# Rpi_Interface.net
KiCad netlist of a schematic drawn in EAGLE
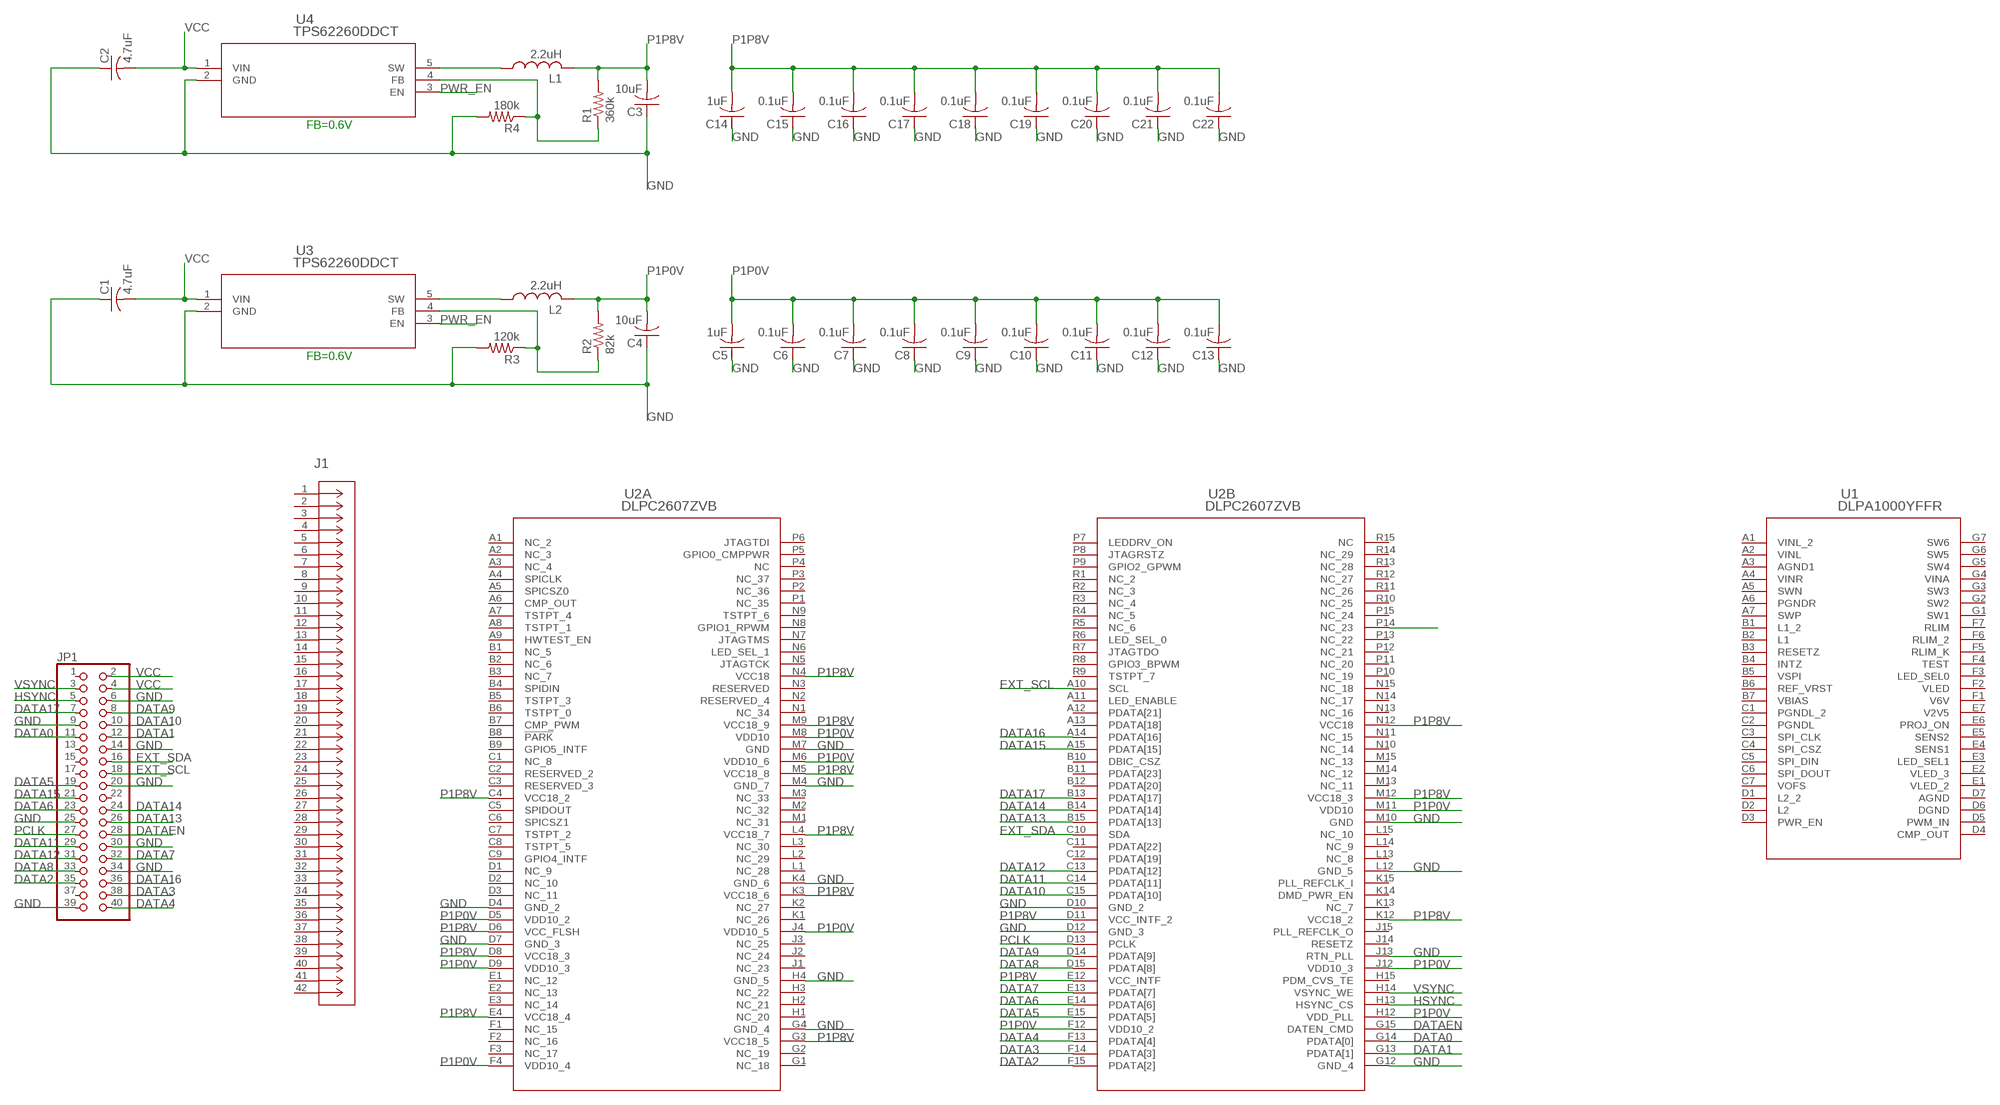
[diagram p0: schematic, sheet 1]

(export (version "E")
  (design (tool "Eeschema 10.0.6"))
  (components
    (comp (ref "C1")
      (value "4.7uF")
      (footprint "eagle-import:C0201")
      (libsource (lib "eagle-import") (part "C-USC0201"))
    )
    (comp (ref "C2")
      (value "4.7uF")
      (footprint "eagle-import:C0201")
      (libsource (lib "eagle-import") (part "C-USC0201"))
    )
    (comp (ref "C3")
      (value "10uF")
      (footprint "eagle-import:C0201")
      (libsource (lib "eagle-import") (part "C-USC0201"))
    )
    (comp (ref "C4")
      (value "10uF")
      (footprint "eagle-import:C0201")
      (libsource (lib "eagle-import") (part "C-USC0201"))
    )
    (comp (ref "C5")
      (value "1uF")
      (footprint "eagle-import:C0201")
      (libsource (lib "eagle-import") (part "C-USC0201"))
    )
    (comp (ref "C6")
      (value "0.1uF")
      (footprint "eagle-import:C0201")
      (libsource (lib "eagle-import") (part "C-USC0201"))
    )
    (comp (ref "C7")
      (value "0.1uF")
      (footprint "eagle-import:C0201")
      (libsource (lib "eagle-import") (part "C-USC0201"))
    )
    (comp (ref "C8")
      (value "0.1uF")
      (footprint "eagle-import:C0201")
      (libsource (lib "eagle-import") (part "C-USC0201"))
    )
    (comp (ref "C9")
      (value "0.1uF")
      (footprint "eagle-import:C0201")
      (libsource (lib "eagle-import") (part "C-USC0201"))
    )
    (comp (ref "C10")
      (value "0.1uF")
      (footprint "eagle-import:C0201")
      (libsource (lib "eagle-import") (part "C-USC0201"))
    )
    (comp (ref "C11")
      (value "0.1uF")
      (footprint "eagle-import:C0201")
      (libsource (lib "eagle-import") (part "C-USC0201"))
    )
    (comp (ref "C12")
      (value "0.1uF")
      (footprint "eagle-import:C0201")
      (libsource (lib "eagle-import") (part "C-USC0201"))
    )
    (comp (ref "C13")
      (value "0.1uF")
      (footprint "eagle-import:C0201")
      (libsource (lib "eagle-import") (part "C-USC0201"))
    )
    (comp (ref "C14")
      (value "1uF")
      (footprint "eagle-import:C0201")
      (libsource (lib "eagle-import") (part "C-USC0201"))
    )
    (comp (ref "C15")
      (value "0.1uF")
      (footprint "eagle-import:C0201")
      (libsource (lib "eagle-import") (part "C-USC0201"))
    )
    (comp (ref "C16")
      (value "0.1uF")
      (footprint "eagle-import:C0201")
      (libsource (lib "eagle-import") (part "C-USC0201"))
    )
    (comp (ref "C17")
      (value "0.1uF")
      (footprint "eagle-import:C0201")
      (libsource (lib "eagle-import") (part "C-USC0201"))
    )
    (comp (ref "C18")
      (value "0.1uF")
      (footprint "eagle-import:C0201")
      (libsource (lib "eagle-import") (part "C-USC0201"))
    )
    (comp (ref "C19")
      (value "0.1uF")
      (footprint "eagle-import:C0201")
      (libsource (lib "eagle-import") (part "C-USC0201"))
    )
    (comp (ref "C20")
      (value "0.1uF")
      (footprint "eagle-import:C0201")
      (libsource (lib "eagle-import") (part "C-USC0201"))
    )
    (comp (ref "C21")
      (value "0.1uF")
      (footprint "eagle-import:C0201")
      (libsource (lib "eagle-import") (part "C-USC0201"))
    )
    (comp (ref "C22")
      (value "0.1uF")
      (footprint "eagle-import:C0201")
      (libsource (lib "eagle-import") (part "C-USC0201"))
    )
    (comp (ref "J1")
      (value "AXT642124DD1")
      (footprint "eagle-import:CONN_AXT642124_PAN")
      (fields (field (name "COPYRIGHT") "Copyright (C) 2018 Accelerated Designs. All rights reserved"))
      (libsource (lib "eagle-import") (part "AXT642124DD1"))
    )
    (comp (ref "JP1")
      (value "PINHD-2X20")
      (footprint "eagle-import:2X20")
      (libsource (lib "eagle-import") (part "PINHD-2X20"))
    )
    (comp (ref "L1")
      (value "2.2uH")
      (footprint "eagle-import:L0201")
      (libsource (lib "eagle-import") (part "L-USL0201"))
    )
    (comp (ref "L2")
      (value "2.2uH")
      (footprint "eagle-import:L0201")
      (libsource (lib "eagle-import") (part "L-USL0201"))
    )
    (comp (ref "R1")
      (value "360k")
      (footprint "eagle-import:0204V")
      (libsource (lib "eagle-import") (part "R-US_0204/2V"))
    )
    (comp (ref "R2")
      (value "82k")
      (footprint "eagle-import:0204V")
      (libsource (lib "eagle-import") (part "R-US_0204/2V"))
    )
    (comp (ref "R3")
      (value "120k")
      (footprint "eagle-import:0204V")
      (libsource (lib "eagle-import") (part "R-US_0204/2V"))
    )
    (comp (ref "R4")
      (value "180k")
      (footprint "eagle-import:0204V")
      (libsource (lib "eagle-import") (part "R-US_0204/2V"))
    )
    (comp (ref "U1")
      (value "DLPA1000YFFR")
      (footprint "eagle-import:YFF49_TEX")
      (fields (field (name "COPYRIGHT") "Copyright (C) 2018 Accelerated Designs. All rights reserved"))
      (libsource (lib "eagle-import") (part "DLPA1000YFFR"))
    )
    (comp (ref "U2")
      (value "DLPC2607ZVB")
      (footprint "eagle-import:ZVB176_TEX")
      (libsource (lib "eagle-import") (part "DLPC2607ZVB"))
    )
    (comp (ref "U3")
      (value "TPS62260DDCT")
      (footprint "eagle-import:DDC5")
      (fields
        (field (name "GENERIC_PART_NUMBER") "TPS62260")
        (field (name "MANUFACTURER") "Texas Instruments")
      )
      (libsource (lib "eagle-import") (part "TPS62260DDCT"))
    )
    (comp (ref "U4")
      (value "TPS62260DDCT")
      (footprint "eagle-import:DDC5")
      (fields
        (field (name "GENERIC_PART_NUMBER") "TPS62260")
        (field (name "MANUFACTURER") "Texas Instruments")
      )
      (libsource (lib "eagle-import") (part "TPS62260DDCT"))
    )
  )
  (nets
    (net (code "1") (name "/AGND") (class "Default")
      (node (ref "U1") (pin "D7") (pinfunction "AGND_D7") (pintype "power_in"))
    )
    (net (code "2") (name "/AGND1") (class "Default")
      (node (ref "U1") (pin "A3") (pinfunction "AGND1_A3") (pintype "power_in"))
    )
    (net (code "3") (name "/DATA0") (class "Default")
      (node (ref "JP1") (pin "11") (pinfunction "11_11") (pintype "passive"))
      (node (ref "U2") (pin "G14") (pinfunction "PDATA[0]_G14") (pintype "input"))
    )
    (net (code "4") (name "/DATA1") (class "Default")
      (node (ref "JP1") (pin "12") (pinfunction "12_12") (pintype "passive"))
      (node (ref "U2") (pin "G13") (pinfunction "PDATA[1]_G13") (pintype "input"))
    )
    (net (code "5") (name "/DATA2") (class "Default")
      (node (ref "JP1") (pin "35") (pinfunction "35_35") (pintype "passive"))
      (node (ref "U2") (pin "F15") (pinfunction "PDATA[2]_F15") (pintype "input"))
    )
    (net (code "6") (name "/DATA3") (class "Default")
      (node (ref "JP1") (pin "38") (pinfunction "38_38") (pintype "passive"))
      (node (ref "U2") (pin "F14") (pinfunction "PDATA[3]_F14") (pintype "input"))
    )
    (net (code "7") (name "/DATA4") (class "Default")
      (node (ref "JP1") (pin "40") (pinfunction "40_40") (pintype "passive"))
      (node (ref "U2") (pin "F13") (pinfunction "PDATA[4]_F13") (pintype "input"))
    )
    (net (code "8") (name "/DATA5") (class "Default")
      (node (ref "JP1") (pin "19") (pinfunction "19_19") (pintype "passive"))
      (node (ref "U2") (pin "E15") (pinfunction "PDATA[5]_E15") (pintype "input"))
    )
    (net (code "9") (name "/DATA6") (class "Default")
      (node (ref "JP1") (pin "23") (pinfunction "23_23") (pintype "passive"))
      (node (ref "U2") (pin "E14") (pinfunction "PDATA[6]_E14") (pintype "input"))
    )
    (net (code "10") (name "/DATA7") (class "Default")
      (node (ref "JP1") (pin "32") (pinfunction "32_32") (pintype "passive"))
      (node (ref "U2") (pin "E13") (pinfunction "PDATA[7]_E13") (pintype "input"))
    )
    (net (code "11") (name "/DATA8") (class "Default")
      (node (ref "JP1") (pin "33") (pinfunction "33_33") (pintype "passive"))
      (node (ref "U2") (pin "D15") (pinfunction "PDATA[8]_D15") (pintype "input"))
    )
    (net (code "12") (name "/DATA9") (class "Default")
      (node (ref "JP1") (pin "8") (pinfunction "8_8") (pintype "passive"))
      (node (ref "U2") (pin "D14") (pinfunction "PDATA[9]_D14") (pintype "input"))
    )
    (net (code "13") (name "/DATA10") (class "Default")
      (node (ref "JP1") (pin "10") (pinfunction "10_10") (pintype "passive"))
      (node (ref "U2") (pin "C15") (pinfunction "PDATA[10]_C15") (pintype "input"))
    )
    (net (code "14") (name "/DATA11") (class "Default")
      (node (ref "JP1") (pin "29") (pinfunction "29_29") (pintype "passive"))
      (node (ref "U2") (pin "C14") (pinfunction "PDATA[11]_C14") (pintype "input"))
    )
    (net (code "15") (name "/DATA12") (class "Default")
      (node (ref "JP1") (pin "31") (pinfunction "31_31") (pintype "passive"))
      (node (ref "U2") (pin "C13") (pinfunction "PDATA[12]_C13") (pintype "input"))
    )
    (net (code "16") (name "/DATA13") (class "Default")
      (node (ref "JP1") (pin "26") (pinfunction "26_26") (pintype "passive"))
      (node (ref "U2") (pin "B15") (pinfunction "PDATA[13]_B15") (pintype "input"))
    )
    (net (code "17") (name "/DATA14") (class "Default")
      (node (ref "JP1") (pin "24") (pinfunction "24_24") (pintype "passive"))
      (node (ref "U2") (pin "B14") (pinfunction "PDATA[14]_B14") (pintype "input"))
    )
    (net (code "18") (name "/DATA15") (class "Default")
      (node (ref "JP1") (pin "21") (pinfunction "21_21") (pintype "passive"))
      (node (ref "U2") (pin "A15") (pinfunction "PDATA[15]_A15") (pintype "input"))
    )
    (net (code "19") (name "/DATA16") (class "Default")
      (node (ref "JP1") (pin "36") (pinfunction "36_36") (pintype "passive"))
      (node (ref "U2") (pin "A14") (pinfunction "PDATA[16]_A14") (pintype "input"))
    )
    (net (code "20") (name "/DATA17") (class "Default")
      (node (ref "JP1") (pin "7") (pinfunction "7_7") (pintype "passive"))
      (node (ref "U2") (pin "B13") (pinfunction "PDATA[17]_B13") (pintype "input"))
    )
    (net (code "21") (name "/DATAEN") (class "Default")
      (node (ref "JP1") (pin "28") (pinfunction "28_28") (pintype "passive"))
      (node (ref "U2") (pin "G15") (pinfunction "DATEN_CMD_G15") (pintype "input"))
    )
    (net (code "22") (name "/DGND") (class "Default")
      (node (ref "U1") (pin "D6") (pinfunction "DGND_D6") (pintype "power_in"))
    )
    (net (code "23") (name "/EXT_SCL") (class "Default")
      (node (ref "JP1") (pin "18") (pinfunction "18_18") (pintype "passive"))
      (node (ref "U2") (pin "A10") (pinfunction "SCL_A10") (pintype "bidirectional"))
    )
    (net (code "24") (name "/EXT_SDA") (class "Default")
      (node (ref "JP1") (pin "16") (pinfunction "16_16") (pintype "passive"))
      (node (ref "U2") (pin "C10") (pinfunction "SDA_C10") (pintype "bidirectional"))
    )
    (net (code "25") (name "/GND") (class "Default")
      (node (ref "C1") (pin "1") (pinfunction "1_1") (pintype "passive"))
      (node (ref "C10") (pin "1") (pinfunction "1_1") (pintype "passive"))
      (node (ref "C11") (pin "1") (pinfunction "1_1") (pintype "passive"))
      (node (ref "C12") (pin "1") (pinfunction "1_1") (pintype "passive"))
      (node (ref "C13") (pin "1") (pinfunction "1_1") (pintype "passive"))
      (node (ref "C14") (pin "1") (pinfunction "1_1") (pintype "passive"))
      (node (ref "C15") (pin "1") (pinfunction "1_1") (pintype "passive"))
      (node (ref "C16") (pin "1") (pinfunction "1_1") (pintype "passive"))
      (node (ref "C17") (pin "1") (pinfunction "1_1") (pintype "passive"))
      (node (ref "C18") (pin "1") (pinfunction "1_1") (pintype "passive"))
      (node (ref "C19") (pin "1") (pinfunction "1_1") (pintype "passive"))
      (node (ref "C2") (pin "1") (pinfunction "1_1") (pintype "passive"))
      (node (ref "C20") (pin "1") (pinfunction "1_1") (pintype "passive"))
      (node (ref "C21") (pin "1") (pinfunction "1_1") (pintype "passive"))
      (node (ref "C22") (pin "1") (pinfunction "1_1") (pintype "passive"))
      (node (ref "C3") (pin "1") (pinfunction "1_1") (pintype "passive"))
      (node (ref "C4") (pin "1") (pinfunction "1_1") (pintype "passive"))
      (node (ref "C5") (pin "1") (pinfunction "1_1") (pintype "passive"))
      (node (ref "C6") (pin "1") (pinfunction "1_1") (pintype "passive"))
      (node (ref "C7") (pin "1") (pinfunction "1_1") (pintype "passive"))
      (node (ref "C8") (pin "1") (pinfunction "1_1") (pintype "passive"))
      (node (ref "C9") (pin "1") (pinfunction "1_1") (pintype "passive"))
      (node (ref "JP1") (pin "14") (pinfunction "14_14") (pintype "passive"))
      (node (ref "JP1") (pin "20") (pinfunction "20_20") (pintype "passive"))
      (node (ref "JP1") (pin "25") (pinfunction "25_25") (pintype "passive"))
      (node (ref "JP1") (pin "30") (pinfunction "30_30") (pintype "passive"))
      (node (ref "JP1") (pin "34") (pinfunction "34_34") (pintype "passive"))
      (node (ref "JP1") (pin "39") (pinfunction "39_39") (pintype "passive"))
      (node (ref "JP1") (pin "6") (pinfunction "6_6") (pintype "passive"))
      (node (ref "JP1") (pin "9") (pinfunction "9_9") (pintype "passive"))
      (node (ref "R3") (pin "2") (pinfunction "2_2") (pintype "passive"))
      (node (ref "R4") (pin "2") (pinfunction "2_2") (pintype "passive"))
      (node (ref "U2") (pin "D10") (pinfunction "GND_2_D10") (pintype "power_in"))
      (node (ref "U2") (pin "D12") (pinfunction "GND_3_D12") (pintype "power_in"))
      (node (ref "U2") (pin "D4") (pinfunction "GND_2_D4") (pintype "power_in"))
      (node (ref "U2") (pin "D7") (pinfunction "GND_3_D7") (pintype "power_in"))
      (node (ref "U2") (pin "G12") (pinfunction "GND_4_G12") (pintype "power_in"))
      (node (ref "U2") (pin "G4") (pinfunction "GND_4_G4") (pintype "power_in"))
      (node (ref "U2") (pin "H4") (pinfunction "GND_5_H4") (pintype "power_in"))
      (node (ref "U2") (pin "J13") (pinfunction "RTN_PLL_J13") (pintype "passive"))
      (node (ref "U2") (pin "K4") (pinfunction "GND_6_K4") (pintype "power_in"))
      (node (ref "U2") (pin "L12") (pinfunction "GND_5_L12") (pintype "power_in"))
      (node (ref "U2") (pin "M10") (pinfunction "GND_M10") (pintype "power_in"))
      (node (ref "U2") (pin "M4") (pinfunction "GND_7_M4") (pintype "power_in"))
      (node (ref "U2") (pin "M7") (pinfunction "GND_M7") (pintype "power_in"))
      (node (ref "U3") (pin "2") (pinfunction "GND_2") (pintype "power_in"))
      (node (ref "U4") (pin "2") (pinfunction "GND_2") (pintype "power_in"))
    )
    (net (code "26") (name "/HSYNC") (class "Default")
      (node (ref "JP1") (pin "5") (pinfunction "5_5") (pintype "passive"))
      (node (ref "U2") (pin "H13") (pinfunction "HSYNC_CS_H13") (pintype "input"))
    )
    (net (code "27") (name "/P1P0V") (class "Default")
      (node (ref "C10") (pin "2") (pinfunction "2_2") (pintype "passive"))
      (node (ref "C11") (pin "2") (pinfunction "2_2") (pintype "passive"))
      (node (ref "C12") (pin "2") (pinfunction "2_2") (pintype "passive"))
      (node (ref "C13") (pin "2") (pinfunction "2_2") (pintype "passive"))
      (node (ref "C4") (pin "2") (pinfunction "2_2") (pintype "passive"))
      (node (ref "C5") (pin "2") (pinfunction "2_2") (pintype "passive"))
      (node (ref "C6") (pin "2") (pinfunction "2_2") (pintype "passive"))
      (node (ref "C7") (pin "2") (pinfunction "2_2") (pintype "passive"))
      (node (ref "C8") (pin "2") (pinfunction "2_2") (pintype "passive"))
      (node (ref "C9") (pin "2") (pinfunction "2_2") (pintype "passive"))
      (node (ref "L2") (pin "2") (pinfunction "2_2") (pintype "passive"))
      (node (ref "R2") (pin "2") (pinfunction "2_2") (pintype "passive"))
      (node (ref "U2") (pin "D5") (pinfunction "VDD10_2_D5") (pintype "power_in"))
      (node (ref "U2") (pin "D9") (pinfunction "VDD10_3_D9") (pintype "power_in"))
      (node (ref "U2") (pin "F12") (pinfunction "VDD10_2_F12") (pintype "power_in"))
      (node (ref "U2") (pin "F4") (pinfunction "VDD10_4_F4") (pintype "power_in"))
      (node (ref "U2") (pin "H12") (pinfunction "VDD_PLL_H12") (pintype "power_in"))
      (node (ref "U2") (pin "J12") (pinfunction "VDD10_3_J12") (pintype "power_in"))
      (node (ref "U2") (pin "J4") (pinfunction "VDD10_5_J4") (pintype "power_in"))
      (node (ref "U2") (pin "M11") (pinfunction "VDD10_M11") (pintype "power_in"))
      (node (ref "U2") (pin "M6") (pinfunction "VDD10_6_M6") (pintype "power_in"))
      (node (ref "U2") (pin "M8") (pinfunction "VDD10_M8") (pintype "power_in"))
    )
    (net (code "28") (name "/P1P8V") (class "Default")
      (node (ref "C14") (pin "2") (pinfunction "2_2") (pintype "passive"))
      (node (ref "C15") (pin "2") (pinfunction "2_2") (pintype "passive"))
      (node (ref "C16") (pin "2") (pinfunction "2_2") (pintype "passive"))
      (node (ref "C17") (pin "2") (pinfunction "2_2") (pintype "passive"))
      (node (ref "C18") (pin "2") (pinfunction "2_2") (pintype "passive"))
      (node (ref "C19") (pin "2") (pinfunction "2_2") (pintype "passive"))
      (node (ref "C20") (pin "2") (pinfunction "2_2") (pintype "passive"))
      (node (ref "C21") (pin "2") (pinfunction "2_2") (pintype "passive"))
      (node (ref "C22") (pin "2") (pinfunction "2_2") (pintype "passive"))
      (node (ref "C3") (pin "2") (pinfunction "2_2") (pintype "passive"))
      (node (ref "L1") (pin "2") (pinfunction "2_2") (pintype "passive"))
      (node (ref "R1") (pin "2") (pinfunction "2_2") (pintype "passive"))
      (node (ref "U2") (pin "C4") (pinfunction "VCC18_2_C4") (pintype "power_in"))
      (node (ref "U2") (pin "D11") (pinfunction "VCC_INTF_2_D11") (pintype "power_in"))
      (node (ref "U2") (pin "D6") (pinfunction "VCC_FLSH_D6") (pintype "power_in"))
      (node (ref "U2") (pin "D8") (pinfunction "VCC18_3_D8") (pintype "power_in"))
      (node (ref "U2") (pin "E12") (pinfunction "VCC_INTF_E12") (pintype "power_in"))
      (node (ref "U2") (pin "E4") (pinfunction "VCC18_4_E4") (pintype "power_in"))
      (node (ref "U2") (pin "G3") (pinfunction "VCC18_5_G3") (pintype "power_in"))
      (node (ref "U2") (pin "K12") (pinfunction "VCC18_2_K12") (pintype "power_in"))
      (node (ref "U2") (pin "K3") (pinfunction "VCC18_6_K3") (pintype "power_in"))
      (node (ref "U2") (pin "L4") (pinfunction "VCC18_7_L4") (pintype "power_in"))
      (node (ref "U2") (pin "M12") (pinfunction "VCC18_3_M12") (pintype "power_in"))
      (node (ref "U2") (pin "M5") (pinfunction "VCC18_8_M5") (pintype "power_in"))
      (node (ref "U2") (pin "M9") (pinfunction "VCC18_9_M9") (pintype "power_in"))
      (node (ref "U2") (pin "N12") (pinfunction "VCC18_N12") (pintype "power_in"))
      (node (ref "U2") (pin "N4") (pinfunction "VCC18_N4") (pintype "power_in"))
    )
    (net (code "29") (name "/PCLK") (class "Default")
      (node (ref "JP1") (pin "27") (pinfunction "27_27") (pintype "passive"))
      (node (ref "U2") (pin "D13") (pinfunction "PCLK_D13") (pintype "input"))
    )
    (net (code "30") (name "/PGNDL") (class "Default")
      (node (ref "U1") (pin "C2") (pinfunction "PGNDL_C2") (pintype "power_in"))
    )
    (net (code "31") (name "/PGNDL_2") (class "Default")
      (node (ref "U1") (pin "C1") (pinfunction "PGNDL_2_C1") (pintype "power_in"))
    )
    (net (code "32") (name "/PGNDR") (class "Default")
      (node (ref "U1") (pin "A6") (pinfunction "PGNDR_A6") (pintype "power_in"))
    )
    (net (code "33") (name "/PWR_EN") (class "Default")
      (node (ref "U3") (pin "3") (pinfunction "EN_3") (pintype "input"))
      (node (ref "U4") (pin "3") (pinfunction "EN_3") (pintype "input"))
    )
    (net (code "34") (name "/VCC") (class "Default")
      (node (ref "C1") (pin "2") (pinfunction "2_2") (pintype "passive"))
      (node (ref "C2") (pin "2") (pinfunction "2_2") (pintype "passive"))
      (node (ref "JP1") (pin "2") (pinfunction "2_2") (pintype "passive"))
      (node (ref "JP1") (pin "4") (pinfunction "4_4") (pintype "passive"))
      (node (ref "U3") (pin "1") (pinfunction "VIN_1") (pintype "power_in"))
      (node (ref "U4") (pin "1") (pinfunction "VIN_1") (pintype "power_in"))
    )
    (net (code "35") (name "/VSPI") (class "Default")
      (node (ref "U1") (pin "B5") (pinfunction "VSPI_B5") (pintype "power_in"))
    )
    (net (code "36") (name "/VSYNC") (class "Default")
      (node (ref "JP1") (pin "3") (pinfunction "3_3") (pintype "passive"))
      (node (ref "U2") (pin "H14") (pinfunction "VSYNC_WE_H14") (pintype "input"))
    )
    (net (code "37") (name "Net-(U3-FB)") (class "Default")
      (node (ref "R2") (pin "1") (pinfunction "1_1") (pintype "passive"))
      (node (ref "R3") (pin "1") (pinfunction "1_1") (pintype "passive"))
      (node (ref "U3") (pin "4") (pinfunction "FB_4") (pintype "input"))
    )
    (net (code "38") (name "Net-(U3-SW)") (class "Default")
      (node (ref "L2") (pin "1") (pinfunction "1_1") (pintype "passive"))
      (node (ref "U3") (pin "5") (pinfunction "SW_5") (pintype "output"))
    )
    (net (code "39") (name "Net-(U4-FB)") (class "Default")
      (node (ref "R1") (pin "1") (pinfunction "1_1") (pintype "passive"))
      (node (ref "R4") (pin "1") (pinfunction "1_1") (pintype "passive"))
      (node (ref "U4") (pin "4") (pinfunction "FB_4") (pintype "input"))
    )
    (net (code "40") (name "Net-(U4-SW)") (class "Default")
      (node (ref "L1") (pin "1") (pinfunction "1_1") (pintype "passive"))
      (node (ref "U4") (pin "5") (pinfunction "SW_5") (pintype "output"))
    )
    (net (code "41") (name "unconnected-(J1-Pad1)") (class "Default")
      (node (ref "J1") (pin "1") (pinfunction "1_1") (pintype "passive"))
    )
    (net (code "42") (name "unconnected-(J1-Pad2)") (class "Default")
      (node (ref "J1") (pin "2") (pinfunction "2_2") (pintype "passive"))
    )
    (net (code "43") (name "unconnected-(J1-Pad3)") (class "Default")
      (node (ref "J1") (pin "3") (pinfunction "3_3") (pintype "passive"))
    )
    (net (code "44") (name "unconnected-(J1-Pad4)") (class "Default")
      (node (ref "J1") (pin "4") (pinfunction "4_4") (pintype "passive"))
    )
    (net (code "45") (name "unconnected-(J1-Pad5)") (class "Default")
      (node (ref "J1") (pin "5") (pinfunction "5_5") (pintype "passive"))
    )
    (net (code "46") (name "unconnected-(J1-Pad6)") (class "Default")
      (node (ref "J1") (pin "6") (pinfunction "6_6") (pintype "passive"))
    )
    (net (code "47") (name "unconnected-(J1-Pad7)") (class "Default")
      (node (ref "J1") (pin "7") (pinfunction "7_7") (pintype "passive"))
    )
    (net (code "48") (name "unconnected-(J1-Pad8)") (class "Default")
      (node (ref "J1") (pin "8") (pinfunction "8_8") (pintype "passive"))
    )
    (net (code "49") (name "unconnected-(J1-Pad9)") (class "Default")
      (node (ref "J1") (pin "9") (pinfunction "9_9") (pintype "passive"))
    )
    (net (code "50") (name "unconnected-(J1-Pad10)") (class "Default")
      (node (ref "J1") (pin "10") (pinfunction "10_10") (pintype "passive"))
    )
    (net (code "51") (name "unconnected-(J1-Pad11)") (class "Default")
      (node (ref "J1") (pin "11") (pinfunction "11_11") (pintype "passive"))
    )
    (net (code "52") (name "unconnected-(J1-Pad12)") (class "Default")
      (node (ref "J1") (pin "12") (pinfunction "12_12") (pintype "passive"))
    )
    (net (code "53") (name "unconnected-(J1-Pad13)") (class "Default")
      (node (ref "J1") (pin "13") (pinfunction "13_13") (pintype "passive"))
    )
    (net (code "54") (name "unconnected-(J1-Pad14)") (class "Default")
      (node (ref "J1") (pin "14") (pinfunction "14_14") (pintype "passive"))
    )
    (net (code "55") (name "unconnected-(J1-Pad15)") (class "Default")
      (node (ref "J1") (pin "15") (pinfunction "15_15") (pintype "passive"))
    )
    (net (code "56") (name "unconnected-(J1-Pad16)") (class "Default")
      (node (ref "J1") (pin "16") (pinfunction "16_16") (pintype "passive"))
    )
    (net (code "57") (name "unconnected-(J1-Pad17)") (class "Default")
      (node (ref "J1") (pin "17") (pinfunction "17_17") (pintype "passive"))
    )
    (net (code "58") (name "unconnected-(J1-Pad18)") (class "Default")
      (node (ref "J1") (pin "18") (pinfunction "18_18") (pintype "passive"))
    )
    (net (code "59") (name "unconnected-(J1-Pad19)") (class "Default")
      (node (ref "J1") (pin "19") (pinfunction "19_19") (pintype "passive"))
    )
    (net (code "60") (name "unconnected-(J1-Pad20)") (class "Default")
      (node (ref "J1") (pin "20") (pinfunction "20_20") (pintype "passive"))
    )
    (net (code "61") (name "unconnected-(J1-Pad21)") (class "Default")
      (node (ref "J1") (pin "21") (pinfunction "21_21") (pintype "passive"))
    )
    (net (code "62") (name "unconnected-(J1-Pad22)") (class "Default")
      (node (ref "J1") (pin "22") (pinfunction "22_22") (pintype "passive"))
    )
    (net (code "63") (name "unconnected-(J1-Pad23)") (class "Default")
      (node (ref "J1") (pin "23") (pinfunction "23_23") (pintype "passive"))
    )
    (net (code "64") (name "unconnected-(J1-Pad24)") (class "Default")
      (node (ref "J1") (pin "24") (pinfunction "24_24") (pintype "passive"))
    )
    (net (code "65") (name "unconnected-(J1-Pad25)") (class "Default")
      (node (ref "J1") (pin "25") (pinfunction "25_25") (pintype "passive"))
    )
    (net (code "66") (name "unconnected-(J1-Pad26)") (class "Default")
      (node (ref "J1") (pin "26") (pinfunction "26_26") (pintype "passive"))
    )
    (net (code "67") (name "unconnected-(J1-Pad27)") (class "Default")
      (node (ref "J1") (pin "27") (pinfunction "27_27") (pintype "passive"))
    )
    (net (code "68") (name "unconnected-(J1-Pad28)") (class "Default")
      (node (ref "J1") (pin "28") (pinfunction "28_28") (pintype "passive"))
    )
    (net (code "69") (name "unconnected-(J1-Pad29)") (class "Default")
      (node (ref "J1") (pin "29") (pinfunction "29_29") (pintype "passive"))
    )
    (net (code "70") (name "unconnected-(J1-Pad30)") (class "Default")
      (node (ref "J1") (pin "30") (pinfunction "30_30") (pintype "passive"))
    )
    (net (code "71") (name "unconnected-(J1-Pad31)") (class "Default")
      (node (ref "J1") (pin "31") (pinfunction "31_31") (pintype "passive"))
    )
    (net (code "72") (name "unconnected-(J1-Pad32)") (class "Default")
      (node (ref "J1") (pin "32") (pinfunction "32_32") (pintype "passive"))
    )
    (net (code "73") (name "unconnected-(J1-Pad33)") (class "Default")
      (node (ref "J1") (pin "33") (pinfunction "33_33") (pintype "passive"))
    )
    (net (code "74") (name "unconnected-(J1-Pad34)") (class "Default")
      (node (ref "J1") (pin "34") (pinfunction "34_34") (pintype "passive"))
    )
    (net (code "75") (name "unconnected-(J1-Pad35)") (class "Default")
      (node (ref "J1") (pin "35") (pinfunction "35_35") (pintype "passive"))
    )
    (net (code "76") (name "unconnected-(J1-Pad36)") (class "Default")
      (node (ref "J1") (pin "36") (pinfunction "36_36") (pintype "passive"))
    )
    (net (code "77") (name "unconnected-(J1-Pad37)") (class "Default")
      (node (ref "J1") (pin "37") (pinfunction "37_37") (pintype "passive"))
    )
    (net (code "78") (name "unconnected-(J1-Pad38)") (class "Default")
      (node (ref "J1") (pin "38") (pinfunction "38_38") (pintype "passive"))
    )
    (net (code "79") (name "unconnected-(J1-Pad39)") (class "Default")
      (node (ref "J1") (pin "39") (pinfunction "39_39") (pintype "passive"))
    )
    (net (code "80") (name "unconnected-(J1-Pad40)") (class "Default")
      (node (ref "J1") (pin "40") (pinfunction "40_40") (pintype "passive"))
    )
    (net (code "81") (name "unconnected-(J1-Pad41)") (class "Default")
      (node (ref "J1") (pin "41") (pinfunction "41_41") (pintype "passive"))
    )
    (net (code "82") (name "unconnected-(J1-Pad42)") (class "Default")
      (node (ref "J1") (pin "42") (pinfunction "42_42") (pintype "passive"))
    )
    (net (code "83") (name "unconnected-(JP1-Pad1)") (class "Default")
      (node (ref "JP1") (pin "1") (pinfunction "1_1") (pintype "passive"))
    )
    (net (code "84") (name "unconnected-(JP1-Pad13)") (class "Default")
      (node (ref "JP1") (pin "13") (pinfunction "13_13") (pintype "passive"))
    )
    (net (code "85") (name "unconnected-(JP1-Pad15)") (class "Default")
      (node (ref "JP1") (pin "15") (pinfunction "15_15") (pintype "passive"))
    )
    (net (code "86") (name "unconnected-(JP1-Pad17)") (class "Default")
      (node (ref "JP1") (pin "17") (pinfunction "17_17") (pintype "passive"))
    )
    (net (code "87") (name "unconnected-(JP1-Pad22)") (class "Default")
      (node (ref "JP1") (pin "22") (pinfunction "22_22") (pintype "passive"))
    )
    (net (code "88") (name "unconnected-(JP1-Pad37)") (class "Default")
      (node (ref "JP1") (pin "37") (pinfunction "37_37") (pintype "passive"))
    )
    (net (code "89") (name "unconnected-(U1-CMP_OUT-PadD4)") (class "Default")
      (node (ref "U1") (pin "D4") (pinfunction "CMP_OUT_D4") (pintype "output"))
    )
    (net (code "90") (name "unconnected-(U1-INTZ-PadB4)") (class "Default")
      (node (ref "U1") (pin "B4") (pinfunction "INTZ_B4") (pintype "output"))
    )
    (net (code "91") (name "unconnected-(U1-L1-PadB2)") (class "Default")
      (node (ref "U1") (pin "B2") (pinfunction "L1_B2") (pintype "input"))
    )
    (net (code "92") (name "unconnected-(U1-L1_2-PadB1)") (class "Default")
      (node (ref "U1") (pin "B1") (pinfunction "L1_2_B1") (pintype "input"))
    )
    (net (code "93") (name "unconnected-(U1-L2-PadD2)") (class "Default")
      (node (ref "U1") (pin "D2") (pinfunction "L2_D2") (pintype "input"))
    )
    (net (code "94") (name "unconnected-(U1-L2_2-PadD1)") (class "Default")
      (node (ref "U1") (pin "D1") (pinfunction "L2_2_D1") (pintype "input"))
    )
    (net (code "95") (name "unconnected-(U1-LED_SEL0-PadF3)") (class "Default")
      (node (ref "U1") (pin "F3") (pinfunction "LED_SEL0_F3") (pintype "input"))
    )
    (net (code "96") (name "unconnected-(U1-LED_SEL1-PadE3)") (class "Default")
      (node (ref "U1") (pin "E3") (pinfunction "LED_SEL1_E3") (pintype "input"))
    )
    (net (code "97") (name "unconnected-(U1-PROJ_ON-PadE6)") (class "Default")
      (node (ref "U1") (pin "E6") (pinfunction "PROJ_ON_E6") (pintype "input"))
    )
    (net (code "98") (name "unconnected-(U1-PWM_IN-PadD5)") (class "Default")
      (node (ref "U1") (pin "D5") (pinfunction "PWM_IN_D5") (pintype "input"))
    )
    (net (code "99") (name "unconnected-(U1-PWR_EN-PadD3)") (class "Default")
      (node (ref "U1") (pin "D3") (pinfunction "PWR_EN_D3") (pintype "output"))
    )
    (net (code "100") (name "unconnected-(U1-REF_VRST-PadB6)") (class "Default")
      (node (ref "U1") (pin "B6") (pinfunction "REF_VRST_B6") (pintype "input"))
    )
    (net (code "101") (name "unconnected-(U1-RESETZ-PadB3)") (class "Default")
      (node (ref "U1") (pin "B3") (pinfunction "RESETZ_B3") (pintype "output"))
    )
    (net (code "102") (name "unconnected-(U1-RLIM-PadF7)") (class "Default")
      (node (ref "U1") (pin "F7") (pinfunction "RLIM_F7") (pintype "output"))
    )
    (net (code "103") (name "unconnected-(U1-RLIM_2-PadF6)") (class "Default")
      (node (ref "U1") (pin "F6") (pinfunction "RLIM_2_F6") (pintype "output"))
    )
    (net (code "104") (name "unconnected-(U1-RLIM_K-PadF5)") (class "Default")
      (node (ref "U1") (pin "F5") (pinfunction "RLIM_K_F5") (pintype "input"))
    )
    (net (code "105") (name "unconnected-(U1-SENS1-PadE4)") (class "Default")
      (node (ref "U1") (pin "E4") (pinfunction "SENS1_E4") (pintype "input"))
    )
    (net (code "106") (name "unconnected-(U1-SENS2-PadE5)") (class "Default")
      (node (ref "U1") (pin "E5") (pinfunction "SENS2_E5") (pintype "input"))
    )
    (net (code "107") (name "unconnected-(U1-SPI_CLK-PadC3)") (class "Default")
      (node (ref "U1") (pin "C3") (pinfunction "SPI_CLK_C3") (pintype "input"))
    )
    (net (code "108") (name "unconnected-(U1-SPI_CSZ-PadC4)") (class "Default")
      (node (ref "U1") (pin "C4") (pinfunction "SPI_CSZ_C4") (pintype "input"))
    )
    (net (code "109") (name "unconnected-(U1-SPI_DIN-PadC5)") (class "Default")
      (node (ref "U1") (pin "C5") (pinfunction "SPI_DIN_C5") (pintype "input"))
    )
    (net (code "110") (name "unconnected-(U1-SPI_DOUT-PadC6)") (class "Default")
      (node (ref "U1") (pin "C6") (pinfunction "SPI_DOUT_C6") (pintype "output"))
    )
    (net (code "111") (name "unconnected-(U1-SW1-PadG1)") (class "Default")
      (node (ref "U1") (pin "G1") (pinfunction "SW1_G1") (pintype "output"))
    )
    (net (code "112") (name "unconnected-(U1-SW2-PadG2)") (class "Default")
      (node (ref "U1") (pin "G2") (pinfunction "SW2_G2") (pintype "output"))
    )
    (net (code "113") (name "unconnected-(U1-SW3-PadG3)") (class "Default")
      (node (ref "U1") (pin "G3") (pinfunction "SW3_G3") (pintype "output"))
    )
    (net (code "114") (name "unconnected-(U1-SW4-PadG5)") (class "Default")
      (node (ref "U1") (pin "G5") (pinfunction "SW4_G5") (pintype "output"))
    )
    (net (code "115") (name "unconnected-(U1-SW5-PadG6)") (class "Default")
      (node (ref "U1") (pin "G6") (pinfunction "SW5_G6") (pintype "output"))
    )
    (net (code "116") (name "unconnected-(U1-SW6-PadG7)") (class "Default")
      (node (ref "U1") (pin "G7") (pinfunction "SW6_G7") (pintype "output"))
    )
    (net (code "117") (name "unconnected-(U1-SWN-PadA5)") (class "Default")
      (node (ref "U1") (pin "A5") (pinfunction "SWN_A5") (pintype "input"))
    )
    (net (code "118") (name "unconnected-(U1-SWP-PadA7)") (class "Default")
      (node (ref "U1") (pin "A7") (pinfunction "SWP_A7") (pintype "input"))
    )
    (net (code "119") (name "unconnected-(U1-TEST-PadF4)") (class "Default")
      (node (ref "U1") (pin "F4") (pinfunction "TEST_F4") (pintype "input"))
    )
    (net (code "120") (name "unconnected-(U1-V2V5-PadE7)") (class "Default")
      (node (ref "U1") (pin "E7") (pinfunction "V2V5_E7") (pintype "output"))
    )
    (net (code "121") (name "unconnected-(U1-V6V-PadF1)") (class "Default")
      (node (ref "U1") (pin "F1") (pinfunction "V6V_F1") (pintype "output"))
    )
    (net (code "122") (name "unconnected-(U1-VBIAS-PadB7)") (class "Default")
      (node (ref "U1") (pin "B7") (pinfunction "VBIAS_B7") (pintype "output"))
    )
    (net (code "123") (name "unconnected-(U1-VINA-PadG4)") (class "Default")
      (node (ref "U1") (pin "G4") (pinfunction "VINA_G4") (pintype "input"))
    )
    (net (code "124") (name "unconnected-(U1-VINL-PadA2)") (class "Default")
      (node (ref "U1") (pin "A2") (pinfunction "VINL_A2") (pintype "input"))
    )
    (net (code "125") (name "unconnected-(U1-VINL_2-PadA1)") (class "Default")
      (node (ref "U1") (pin "A1") (pinfunction "VINL_2_A1") (pintype "input"))
    )
    (net (code "126") (name "unconnected-(U1-VINR-PadA4)") (class "Default")
      (node (ref "U1") (pin "A4") (pinfunction "VINR_A4") (pintype "input"))
    )
    (net (code "127") (name "unconnected-(U1-VLED-PadF2)") (class "Default")
      (node (ref "U1") (pin "F2") (pinfunction "VLED_F2") (pintype "output"))
    )
    (net (code "128") (name "unconnected-(U1-VLED_2-PadE1)") (class "Default")
      (node (ref "U1") (pin "E1") (pinfunction "VLED_2_E1") (pintype "output"))
    )
    (net (code "129") (name "unconnected-(U1-VLED_3-PadE2)") (class "Default")
      (node (ref "U1") (pin "E2") (pinfunction "VLED_3_E2") (pintype "output"))
    )
    (net (code "130") (name "unconnected-(U1-VOFS-PadC7)") (class "Default")
      (node (ref "U1") (pin "C7") (pinfunction "VOFS_C7") (pintype "output"))
    )
    (net (code "131") (name "unconnected-(U2A-CMP_OUT-PadA6)") (class "Default")
      (node (ref "U2") (pin "A6") (pinfunction "CMP_OUT_A6") (pintype "input"))
    )
    (net (code "132") (name "unconnected-(U2A-CMP_PWM-PadB7)") (class "Default")
      (node (ref "U2") (pin "B7") (pinfunction "CMP_PWM_B7") (pintype "output"))
    )
    (net (code "133") (name "unconnected-(U2A-GPIO0_CMPPWR-PadP5)") (class "Default")
      (node (ref "U2") (pin "P5") (pinfunction "GPIO0_CMPPWR_P5") (pintype "bidirectional"))
    )
    (net (code "134") (name "unconnected-(U2A-GPIO1_RPWM-PadN8)") (class "Default")
      (node (ref "U2") (pin "N8") (pinfunction "GPIO1_RPWM_N8") (pintype "output"))
    )
    (net (code "135") (name "unconnected-(U2A-GPIO4_INTF-PadC9)") (class "Default")
      (node (ref "U2") (pin "C9") (pinfunction "GPIO4_INTF_C9") (pintype "bidirectional"))
    )
    (net (code "136") (name "unconnected-(U2A-GPIO5_INTF-PadB9)") (class "Default")
      (node (ref "U2") (pin "B9") (pinfunction "GPIO5_INTF_B9") (pintype "bidirectional"))
    )
    (net (code "137") (name "unconnected-(U2A-HWTEST_EN-PadA9)") (class "Default")
      (node (ref "U2") (pin "A9") (pinfunction "HWTEST_EN_A9") (pintype "input"))
    )
    (net (code "138") (name "unconnected-(U2A-JTAGTCK-PadN5)") (class "Default")
      (node (ref "U2") (pin "N5") (pinfunction "JTAGTCK_N5") (pintype "input"))
    )
    (net (code "139") (name "unconnected-(U2A-JTAGTDI-PadP6)") (class "Default")
      (node (ref "U2") (pin "P6") (pinfunction "JTAGTDI_P6") (pintype "input"))
    )
    (net (code "140") (name "unconnected-(U2A-JTAGTMS-PadN7)") (class "Default")
      (node (ref "U2") (pin "N7") (pinfunction "JTAGTMS_N7") (pintype "input"))
    )
    (net (code "141") (name "unconnected-(U2A-LED_SEL_1-PadN6)") (class "Default")
      (node (ref "U2") (pin "N6") (pinfunction "LED_SEL_1_N6") (pintype "output"))
    )
    (net (code "142") (name "unconnected-(U2A-NC-PadP4)") (class "Default")
      (node (ref "U2") (pin "P4") (pinfunction "NC_P4") (pintype "no_connect"))
    )
    (net (code "143") (name "unconnected-(U2A-NC_2-PadA1)") (class "Default")
      (node (ref "U2") (pin "A1") (pinfunction "NC_2_A1") (pintype "no_connect"))
    )
    (net (code "144") (name "unconnected-(U2A-NC_3-PadA2)") (class "Default")
      (node (ref "U2") (pin "A2") (pinfunction "NC_3_A2") (pintype "no_connect"))
    )
    (net (code "145") (name "unconnected-(U2A-NC_4-PadA3)") (class "Default")
      (node (ref "U2") (pin "A3") (pinfunction "NC_4_A3") (pintype "no_connect"))
    )
    (net (code "146") (name "unconnected-(U2A-NC_5-PadB1)") (class "Default")
      (node (ref "U2") (pin "B1") (pinfunction "NC_5_B1") (pintype "no_connect"))
    )
    (net (code "147") (name "unconnected-(U2A-NC_6-PadB2)") (class "Default")
      (node (ref "U2") (pin "B2") (pinfunction "NC_6_B2") (pintype "no_connect"))
    )
    (net (code "148") (name "unconnected-(U2A-NC_7-PadB3)") (class "Default")
      (node (ref "U2") (pin "B3") (pinfunction "NC_7_B3") (pintype "no_connect"))
    )
    (net (code "149") (name "unconnected-(U2A-NC_8-PadC1)") (class "Default")
      (node (ref "U2") (pin "C1") (pinfunction "NC_8_C1") (pintype "no_connect"))
    )
    (net (code "150") (name "unconnected-(U2A-NC_9-PadD1)") (class "Default")
      (node (ref "U2") (pin "D1") (pinfunction "NC_9_D1") (pintype "no_connect"))
    )
    (net (code "151") (name "unconnected-(U2A-NC_10-PadD2)") (class "Default")
      (node (ref "U2") (pin "D2") (pinfunction "NC_10_D2") (pintype "no_connect"))
    )
    (net (code "152") (name "unconnected-(U2A-NC_11-PadD3)") (class "Default")
      (node (ref "U2") (pin "D3") (pinfunction "NC_11_D3") (pintype "no_connect"))
    )
    (net (code "153") (name "unconnected-(U2A-NC_12-PadE1)") (class "Default")
      (node (ref "U2") (pin "E1") (pinfunction "NC_12_E1") (pintype "no_connect"))
    )
    (net (code "154") (name "unconnected-(U2A-NC_13-PadE2)") (class "Default")
      (node (ref "U2") (pin "E2") (pinfunction "NC_13_E2") (pintype "no_connect"))
    )
    (net (code "155") (name "unconnected-(U2A-NC_14-PadE3)") (class "Default")
      (node (ref "U2") (pin "E3") (pinfunction "NC_14_E3") (pintype "no_connect"))
    )
    (net (code "156") (name "unconnected-(U2A-NC_15-PadF1)") (class "Default")
      (node (ref "U2") (pin "F1") (pinfunction "NC_15_F1") (pintype "no_connect"))
    )
    (net (code "157") (name "unconnected-(U2A-NC_16-PadF2)") (class "Default")
      (node (ref "U2") (pin "F2") (pinfunction "NC_16_F2") (pintype "no_connect"))
    )
    (net (code "158") (name "unconnected-(U2A-NC_17-PadF3)") (class "Default")
      (node (ref "U2") (pin "F3") (pinfunction "NC_17_F3") (pintype "no_connect"))
    )
    (net (code "159") (name "unconnected-(U2A-NC_18-PadG1)") (class "Default")
      (node (ref "U2") (pin "G1") (pinfunction "NC_18_G1") (pintype "no_connect"))
    )
    (net (code "160") (name "unconnected-(U2A-NC_19-PadG2)") (class "Default")
      (node (ref "U2") (pin "G2") (pinfunction "NC_19_G2") (pintype "no_connect"))
    )
    (net (code "161") (name "unconnected-(U2A-NC_20-PadH1)") (class "Default")
      (node (ref "U2") (pin "H1") (pinfunction "NC_20_H1") (pintype "no_connect"))
    )
    (net (code "162") (name "unconnected-(U2A-NC_21-PadH2)") (class "Default")
      (node (ref "U2") (pin "H2") (pinfunction "NC_21_H2") (pintype "no_connect"))
    )
    (net (code "163") (name "unconnected-(U2A-NC_22-PadH3)") (class "Default")
      (node (ref "U2") (pin "H3") (pinfunction "NC_22_H3") (pintype "no_connect"))
    )
    (net (code "164") (name "unconnected-(U2A-NC_23-PadJ1)") (class "Default")
      (node (ref "U2") (pin "J1") (pinfunction "NC_23_J1") (pintype "no_connect"))
    )
    (net (code "165") (name "unconnected-(U2A-NC_24-PadJ2)") (class "Default")
      (node (ref "U2") (pin "J2") (pinfunction "NC_24_J2") (pintype "no_connect"))
    )
    (net (code "166") (name "unconnected-(U2A-NC_25-PadJ3)") (class "Default")
      (node (ref "U2") (pin "J3") (pinfunction "NC_25_J3") (pintype "no_connect"))
    )
    (net (code "167") (name "unconnected-(U2A-NC_26-PadK1)") (class "Default")
      (node (ref "U2") (pin "K1") (pinfunction "NC_26_K1") (pintype "no_connect"))
    )
    (net (code "168") (name "unconnected-(U2A-NC_27-PadK2)") (class "Default")
      (node (ref "U2") (pin "K2") (pinfunction "NC_27_K2") (pintype "no_connect"))
    )
    (net (code "169") (name "unconnected-(U2A-NC_28-PadL1)") (class "Default")
      (node (ref "U2") (pin "L1") (pinfunction "NC_28_L1") (pintype "no_connect"))
    )
    (net (code "170") (name "unconnected-(U2A-NC_29-PadL2)") (class "Default")
      (node (ref "U2") (pin "L2") (pinfunction "NC_29_L2") (pintype "no_connect"))
    )
    (net (code "171") (name "unconnected-(U2A-NC_30-PadL3)") (class "Default")
      (node (ref "U2") (pin "L3") (pinfunction "NC_30_L3") (pintype "no_connect"))
    )
    (net (code "172") (name "unconnected-(U2A-NC_31-PadM1)") (class "Default")
      (node (ref "U2") (pin "M1") (pinfunction "NC_31_M1") (pintype "no_connect"))
    )
    (net (code "173") (name "unconnected-(U2A-NC_32-PadM2)") (class "Default")
      (node (ref "U2") (pin "M2") (pinfunction "NC_32_M2") (pintype "no_connect"))
    )
    (net (code "174") (name "unconnected-(U2A-NC_33-PadM3)") (class "Default")
      (node (ref "U2") (pin "M3") (pinfunction "NC_33_M3") (pintype "no_connect"))
    )
    (net (code "175") (name "unconnected-(U2A-NC_34-PadN1)") (class "Default")
      (node (ref "U2") (pin "N1") (pinfunction "NC_34_N1") (pintype "no_connect"))
    )
    (net (code "176") (name "unconnected-(U2A-NC_35-PadP1)") (class "Default")
      (node (ref "U2") (pin "P1") (pinfunction "NC_35_P1") (pintype "no_connect"))
    )
    (net (code "177") (name "unconnected-(U2A-NC_36-PadP2)") (class "Default")
      (node (ref "U2") (pin "P2") (pinfunction "NC_36_P2") (pintype "no_connect"))
    )
    (net (code "178") (name "unconnected-(U2A-NC_37-PadP3)") (class "Default")
      (node (ref "U2") (pin "P3") (pinfunction "NC_37_P3") (pintype "no_connect"))
    )
    (net (code "179") (name "unconnected-(U2A-RESERVED-PadN3)") (class "Default")
      (node (ref "U2") (pin "N3") (pinfunction "RESERVED_N3") (pintype "passive"))
    )
    (net (code "180") (name "unconnected-(U2A-RESERVED_2-PadC2)") (class "Default")
      (node (ref "U2") (pin "C2") (pinfunction "RESERVED_2_C2") (pintype "passive"))
    )
    (net (code "181") (name "unconnected-(U2A-RESERVED_3-PadC3)") (class "Default")
      (node (ref "U2") (pin "C3") (pinfunction "RESERVED_3_C3") (pintype "passive"))
    )
    (net (code "182") (name "unconnected-(U2A-RESERVED_4-PadN2)") (class "Default")
      (node (ref "U2") (pin "N2") (pinfunction "RESERVED_4_N2") (pintype "passive"))
    )
    (net (code "183") (name "unconnected-(U2A-SPICLK-PadA4)") (class "Default")
      (node (ref "U2") (pin "A4") (pinfunction "SPICLK_A4") (pintype "output"))
    )
    (net (code "184") (name "unconnected-(U2A-SPICSZ0-PadA5)") (class "Default")
      (node (ref "U2") (pin "A5") (pinfunction "SPICSZ0_A5") (pintype "output"))
    )
    (net (code "185") (name "unconnected-(U2A-SPICSZ1-PadC6)") (class "Default")
      (node (ref "U2") (pin "C6") (pinfunction "SPICSZ1_C6") (pintype "output"))
    )
    (net (code "186") (name "unconnected-(U2A-SPIDIN-PadB4)") (class "Default")
      (node (ref "U2") (pin "B4") (pinfunction "SPIDIN_B4") (pintype "input"))
    )
    (net (code "187") (name "unconnected-(U2A-SPIDOUT-PadC5)") (class "Default")
      (node (ref "U2") (pin "C5") (pinfunction "SPIDOUT_C5") (pintype "output"))
    )
    (net (code "188") (name "unconnected-(U2A-TSTPT_0-PadB6)") (class "Default")
      (node (ref "U2") (pin "B6") (pinfunction "TSTPT_0_B6") (pintype "bidirectional"))
    )
    (net (code "189") (name "unconnected-(U2A-TSTPT_1-PadA8)") (class "Default")
      (node (ref "U2") (pin "A8") (pinfunction "TSTPT_1_A8") (pintype "bidirectional"))
    )
    (net (code "190") (name "unconnected-(U2A-TSTPT_2-PadC7)") (class "Default")
      (node (ref "U2") (pin "C7") (pinfunction "TSTPT_2_C7") (pintype "bidirectional"))
    )
    (net (code "191") (name "unconnected-(U2A-TSTPT_3-PadB5)") (class "Default")
      (node (ref "U2") (pin "B5") (pinfunction "TSTPT_3_B5") (pintype "bidirectional"))
    )
    (net (code "192") (name "unconnected-(U2A-TSTPT_4-PadA7)") (class "Default")
      (node (ref "U2") (pin "A7") (pinfunction "TSTPT_4_A7") (pintype "bidirectional"))
    )
    (net (code "193") (name "unconnected-(U2A-TSTPT_5-PadC8)") (class "Default")
      (node (ref "U2") (pin "C8") (pinfunction "TSTPT_5_C8") (pintype "bidirectional"))
    )
    (net (code "194") (name "unconnected-(U2A-TSTPT_6-PadN9)") (class "Default")
      (node (ref "U2") (pin "N9") (pinfunction "TSTPT_6_N9") (pintype "bidirectional"))
    )
    (net (code "195") (name "unconnected-(U2A-~{PARK}-PadB8)") (class "Default")
      (node (ref "U2") (pin "B8") (pinfunction "~{PARK}_B8") (pintype "input"))
    )
    (net (code "196") (name "unconnected-(U2B-DBIC_CSZ-PadB10)") (class "Default")
      (node (ref "U2") (pin "B10") (pinfunction "DBIC_CSZ_B10") (pintype "input"))
    )
    (net (code "197") (name "unconnected-(U2B-DMD_PWR_EN-PadK14)") (class "Default")
      (node (ref "U2") (pin "K14") (pinfunction "DMD_PWR_EN_K14") (pintype "output"))
    )
    (net (code "198") (name "unconnected-(U2B-GPIO2_GPWM-PadP9)") (class "Default")
      (node (ref "U2") (pin "P9") (pinfunction "GPIO2_GPWM_P9") (pintype "output"))
    )
    (net (code "199") (name "unconnected-(U2B-GPIO3_BPWM-PadR8)") (class "Default")
      (node (ref "U2") (pin "R8") (pinfunction "GPIO3_BPWM_R8") (pintype "output"))
    )
    (net (code "200") (name "unconnected-(U2B-JTAGRSTZ-PadP8)") (class "Default")
      (node (ref "U2") (pin "P8") (pinfunction "JTAGRSTZ_P8") (pintype "input"))
    )
    (net (code "201") (name "unconnected-(U2B-JTAGTDO-PadR7)") (class "Default")
      (node (ref "U2") (pin "R7") (pinfunction "JTAGTDO_R7") (pintype "output"))
    )
    (net (code "202") (name "unconnected-(U2B-LEDDRV_ON-PadP7)") (class "Default")
      (node (ref "U2") (pin "P7") (pinfunction "LEDDRV_ON_P7") (pintype "output"))
    )
    (net (code "203") (name "unconnected-(U2B-LED_ENABLE-PadA11)") (class "Default")
      (node (ref "U2") (pin "A11") (pinfunction "LED_ENABLE_A11") (pintype "input"))
    )
    (net (code "204") (name "unconnected-(U2B-LED_SEL_0-PadR6)") (class "Default")
      (node (ref "U2") (pin "R6") (pinfunction "LED_SEL_0_R6") (pintype "output"))
    )
    (net (code "205") (name "unconnected-(U2B-NC-PadR15)") (class "Default")
      (node (ref "U2") (pin "R15") (pinfunction "NC_R15") (pintype "no_connect"))
    )
    (net (code "206") (name "unconnected-(U2B-NC_2-PadR1)") (class "Default")
      (node (ref "U2") (pin "R1") (pinfunction "NC_2_R1") (pintype "no_connect"))
    )
    (net (code "207") (name "unconnected-(U2B-NC_3-PadR2)") (class "Default")
      (node (ref "U2") (pin "R2") (pinfunction "NC_3_R2") (pintype "no_connect"))
    )
    (net (code "208") (name "unconnected-(U2B-NC_4-PadR3)") (class "Default")
      (node (ref "U2") (pin "R3") (pinfunction "NC_4_R3") (pintype "no_connect"))
    )
    (net (code "209") (name "unconnected-(U2B-NC_5-PadR4)") (class "Default")
      (node (ref "U2") (pin "R4") (pinfunction "NC_5_R4") (pintype "no_connect"))
    )
    (net (code "210") (name "unconnected-(U2B-NC_6-PadR5)") (class "Default")
      (node (ref "U2") (pin "R5") (pinfunction "NC_6_R5") (pintype "no_connect"))
    )
    (net (code "211") (name "unconnected-(U2B-NC_7-PadK13)") (class "Default")
      (node (ref "U2") (pin "K13") (pinfunction "NC_7_K13") (pintype "no_connect"))
    )
    (net (code "212") (name "unconnected-(U2B-NC_8-PadL13)") (class "Default")
      (node (ref "U2") (pin "L13") (pinfunction "NC_8_L13") (pintype "no_connect"))
    )
    (net (code "213") (name "unconnected-(U2B-NC_9-PadL14)") (class "Default")
      (node (ref "U2") (pin "L14") (pinfunction "NC_9_L14") (pintype "no_connect"))
    )
    (net (code "214") (name "unconnected-(U2B-NC_10-PadL15)") (class "Default")
      (node (ref "U2") (pin "L15") (pinfunction "NC_10_L15") (pintype "no_connect"))
    )
    (net (code "215") (name "unconnected-(U2B-NC_11-PadM13)") (class "Default")
      (node (ref "U2") (pin "M13") (pinfunction "NC_11_M13") (pintype "no_connect"))
    )
    (net (code "216") (name "unconnected-(U2B-NC_12-PadM14)") (class "Default")
      (node (ref "U2") (pin "M14") (pinfunction "NC_12_M14") (pintype "no_connect"))
    )
    (net (code "217") (name "unconnected-(U2B-NC_13-PadM15)") (class "Default")
      (node (ref "U2") (pin "M15") (pinfunction "NC_13_M15") (pintype "no_connect"))
    )
    (net (code "218") (name "unconnected-(U2B-NC_14-PadN10)") (class "Default")
      (node (ref "U2") (pin "N10") (pinfunction "NC_14_N10") (pintype "no_connect"))
    )
    (net (code "219") (name "unconnected-(U2B-NC_15-PadN11)") (class "Default")
      (node (ref "U2") (pin "N11") (pinfunction "NC_15_N11") (pintype "no_connect"))
    )
    (net (code "220") (name "unconnected-(U2B-NC_16-PadN13)") (class "Default")
      (node (ref "U2") (pin "N13") (pinfunction "NC_16_N13") (pintype "no_connect"))
    )
    (net (code "221") (name "unconnected-(U2B-NC_17-PadN14)") (class "Default")
      (node (ref "U2") (pin "N14") (pinfunction "NC_17_N14") (pintype "no_connect"))
    )
    (net (code "222") (name "unconnected-(U2B-NC_18-PadN15)") (class "Default")
      (node (ref "U2") (pin "N15") (pinfunction "NC_18_N15") (pintype "no_connect"))
    )
    (net (code "223") (name "unconnected-(U2B-NC_19-PadP10)") (class "Default")
      (node (ref "U2") (pin "P10") (pinfunction "NC_19_P10") (pintype "no_connect"))
    )
    (net (code "224") (name "unconnected-(U2B-NC_20-PadP11)") (class "Default")
      (node (ref "U2") (pin "P11") (pinfunction "NC_20_P11") (pintype "no_connect"))
    )
    (net (code "225") (name "unconnected-(U2B-NC_21-PadP12)") (class "Default")
      (node (ref "U2") (pin "P12") (pinfunction "NC_21_P12") (pintype "no_connect"))
    )
    (net (code "226") (name "unconnected-(U2B-NC_22-PadP13)") (class "Default")
      (node (ref "U2") (pin "P13") (pinfunction "NC_22_P13") (pintype "no_connect"))
    )
    (net (code "227") (name "unconnected-(U2B-NC_23-PadP14)") (class "Default")
      (node (ref "U2") (pin "P14") (pinfunction "NC_23_P14") (pintype "no_connect"))
    )
    (net (code "228") (name "unconnected-(U2B-NC_24-PadP15)") (class "Default")
      (node (ref "U2") (pin "P15") (pinfunction "NC_24_P15") (pintype "no_connect"))
    )
    (net (code "229") (name "unconnected-(U2B-NC_25-PadR10)") (class "Default")
      (node (ref "U2") (pin "R10") (pinfunction "NC_25_R10") (pintype "no_connect"))
    )
    (net (code "230") (name "unconnected-(U2B-NC_26-PadR11)") (class "Default")
      (node (ref "U2") (pin "R11") (pinfunction "NC_26_R11") (pintype "no_connect"))
    )
    (net (code "231") (name "unconnected-(U2B-NC_27-PadR12)") (class "Default")
      (node (ref "U2") (pin "R12") (pinfunction "NC_27_R12") (pintype "no_connect"))
    )
    (net (code "232") (name "unconnected-(U2B-NC_28-PadR13)") (class "Default")
      (node (ref "U2") (pin "R13") (pinfunction "NC_28_R13") (pintype "no_connect"))
    )
    (net (code "233") (name "unconnected-(U2B-NC_29-PadR14)") (class "Default")
      (node (ref "U2") (pin "R14") (pinfunction "NC_29_R14") (pintype "no_connect"))
    )
    (net (code "234") (name "unconnected-(U2B-PDATA[18]-PadA13)") (class "Default")
      (node (ref "U2") (pin "A13") (pinfunction "PDATA[18]_A13") (pintype "input"))
    )
    (net (code "235") (name "unconnected-(U2B-PDATA[19]-PadC12)") (class "Default")
      (node (ref "U2") (pin "C12") (pinfunction "PDATA[19]_C12") (pintype "input"))
    )
    (net (code "236") (name "unconnected-(U2B-PDATA[20]-PadB12)") (class "Default")
      (node (ref "U2") (pin "B12") (pinfunction "PDATA[20]_B12") (pintype "input"))
    )
    (net (code "237") (name "unconnected-(U2B-PDATA[21]-PadA12)") (class "Default")
      (node (ref "U2") (pin "A12") (pinfunction "PDATA[21]_A12") (pintype "input"))
    )
    (net (code "238") (name "unconnected-(U2B-PDATA[22]-PadC11)") (class "Default")
      (node (ref "U2") (pin "C11") (pinfunction "PDATA[22]_C11") (pintype "input"))
    )
    (net (code "239") (name "unconnected-(U2B-PDATA[23]-PadB11)") (class "Default")
      (node (ref "U2") (pin "B11") (pinfunction "PDATA[23]_B11") (pintype "input"))
    )
    (net (code "240") (name "unconnected-(U2B-PDM_CVS_TE-PadH15)") (class "Default")
      (node (ref "U2") (pin "H15") (pinfunction "PDM_CVS_TE_H15") (pintype "bidirectional"))
    )
    (net (code "241") (name "unconnected-(U2B-PLL_REFCLK_I-PadK15)") (class "Default")
      (node (ref "U2") (pin "K15") (pinfunction "PLL_REFCLK_I_K15") (pintype "input"))
    )
    (net (code "242") (name "unconnected-(U2B-PLL_REFCLK_O-PadJ15)") (class "Default")
      (node (ref "U2") (pin "J15") (pinfunction "PLL_REFCLK_O_J15") (pintype "output"))
    )
    (net (code "243") (name "unconnected-(U2B-RESETZ-PadJ14)") (class "Default")
      (node (ref "U2") (pin "J14") (pinfunction "RESETZ_J14") (pintype "input"))
    )
    (net (code "244") (name "unconnected-(U2B-TSTPT_7-PadR9)") (class "Default")
      (node (ref "U2") (pin "R9") (pinfunction "TSTPT_7_R9") (pintype "bidirectional"))
    )
  )
)
